# TVHR-PIDer.net
KiCad netlist of a schematic drawn in EAGLE
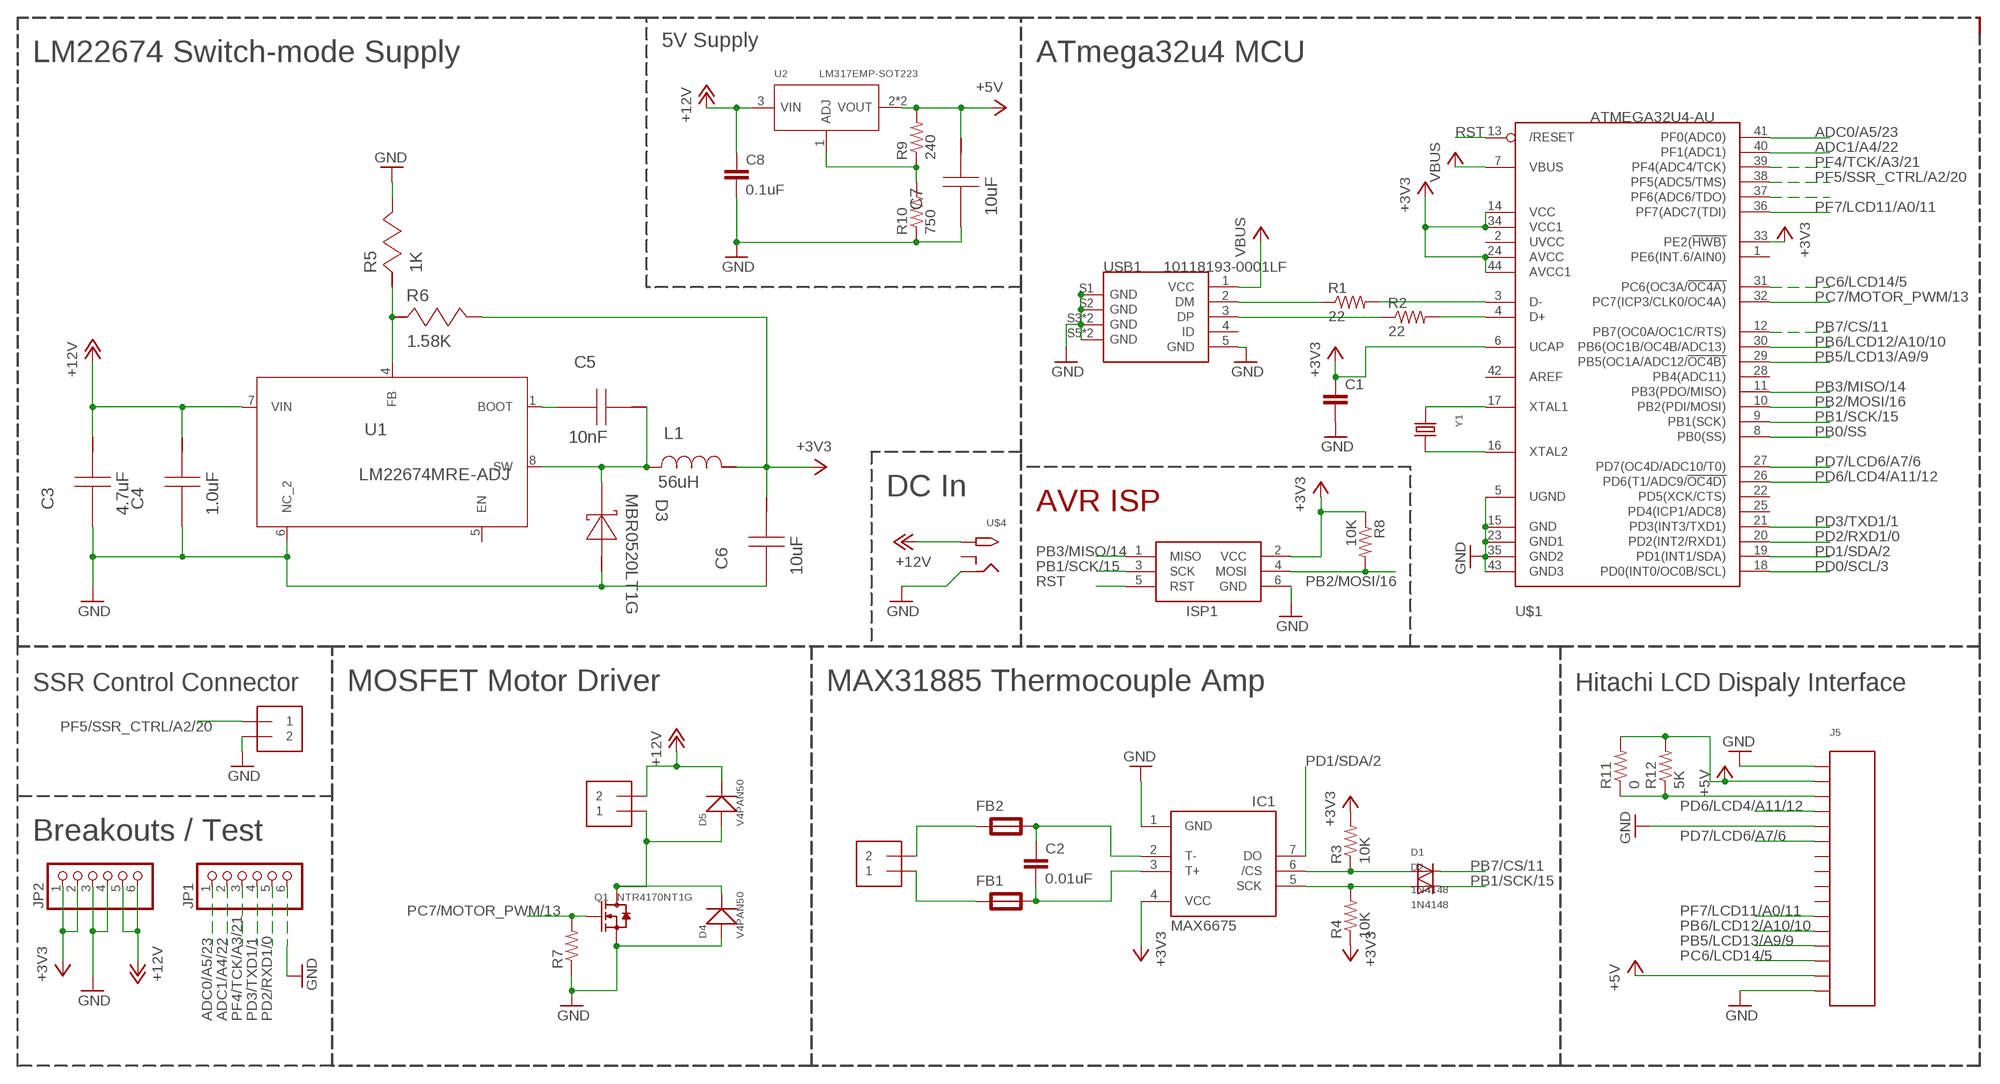
[diagram p0: schematic, sheet 1]

(export (version "E")
  (design (tool "Eeschema 10.0.6"))
  (components
    (comp (ref "C1")
      (value "C-EUC0603")
      (footprint "eagle-import:C0603")
      (libsource (lib "eagle-import") (part "C-EUC0603"))
    )
    (comp (ref "C2")
      (value "0.01uF")
      (footprint "eagle-import:C0603")
      (libsource (lib "eagle-import") (part "C-EUC0603"))
    )
    (comp (ref "C3")
      (value "4.7uF")
      (footprint "eagle-import:0805")
      (fields (field (name "MANUFACTURER_PART_NUMBER") "GRM21BR61E475KA12L"))
      (libsource (lib "eagle-import") (part "GRM21BR61E475KA12L"))
    )
    (comp (ref "C4")
      (value "1.0uF")
      (footprint "eagle-import:0603")
      (fields (field (name "MANUFACTURER_PART_NUMBER") "GRM188R71C105KA12D"))
      (libsource (lib "eagle-import") (part "GRM188R71C105KA12D"))
    )
    (comp (ref "C5")
      (value "10nF")
      (footprint "eagle-import:0805")
      (fields (field (name "MANUFACTURER_PART_NUMBER") "C0805C103K5RACTU"))
      (libsource (lib "eagle-import") (part "C0805C103K5RACTU"))
    )
    (comp (ref "C6")
      (value "10uF")
      (footprint "eagle-import:0805")
      (fields (field (name "MANUFACTURER_PART_NUMBER") "GRM219R60J106KE19D"))
      (libsource (lib "eagle-import") (part "GRM219R60J106KE19D"))
    )
    (comp (ref "C7")
      (value "10uF")
      (footprint "eagle-import:0805")
      (fields (field (name "MANUFACTURER_PART_NUMBER") "GRM219R60J106KE19D"))
      (libsource (lib "eagle-import") (part "GRM219R60J106KE19D"))
    )
    (comp (ref "C8")
      (value "0.1uF")
      (footprint "eagle-import:C0603")
      (libsource (lib "eagle-import") (part "C-EUC0603"))
    )
    (comp (ref "D1")
      (value "1N4148")
      (footprint "eagle-import:SOD-323F")
      (libsource (lib "eagle-import") (part "DIODESOD-323F"))
    )
    (comp (ref "D2")
      (value "1N4148")
      (footprint "eagle-import:SOD-323F")
      (libsource (lib "eagle-import") (part "DIODESOD-323F"))
    )
    (comp (ref "D3")
      (value "MBR0520LT1G")
      (footprint "eagle-import:SOD-123")
      (libsource (lib "eagle-import") (part "MBR0520LT1G"))
    )
    (comp (ref "D4")
      (value "V4PAN50")
      (footprint "eagle-import:SMD-DIODE-DO221BC-2")
      (fields (field (name "MF") "VISHAY"))
      (libsource (lib "eagle-import") (part "SMD-DIODE-50V-4A(DO-221BC)"))
    )
    (comp (ref "D5")
      (value "V4PAN50")
      (footprint "eagle-import:SMD-DIODE-DO221BC-2")
      (fields (field (name "MF") "VISHAY"))
      (libsource (lib "eagle-import") (part "SMD-DIODE-50V-4A(DO-221BC)"))
    )
    (comp (ref "FB1")
      (value "FERRITE-BEAD")
      (footprint "eagle-import:R0805")
      (libsource (lib "eagle-import") (part "FERRITE-BEAD"))
    )
    (comp (ref "FB2")
      (value "FERRITE-BEAD")
      (footprint "eagle-import:R0805")
      (libsource (lib "eagle-import") (part "FERRITE-BEAD"))
    )
    (comp (ref "IC1")
      (value "MAX6675")
      (footprint "eagle-import:SO08")
      (libsource (lib "eagle-import") (part "MAX6675"))
    )
    (comp (ref "ISP1")
      (value "AVRISP-BOX")
      (footprint "eagle-import:AVRISP-BOX")
      (libsource (lib "eagle-import") (part "AVRISP-BOX"))
    )
    (comp (ref "J2")
      (value "1X2-3.5MM")
      (footprint "eagle-import:1X2-3.5MM")
      (libsource (lib "eagle-import") (part "1X2-3.5MM"))
    )
    (comp (ref "J3")
      (value "1X2-3.5MM")
      (footprint "eagle-import:1X2-3.5MM")
      (libsource (lib "eagle-import") (part "1X2-3.5MM"))
    )
    (comp (ref "J4")
      (value "1X2-3.5MM")
      (footprint "eagle-import:1X2-3.5MM")
      (libsource (lib "eagle-import") (part "1X2-3.5MM"))
    )
    (comp (ref "J5")
      (value "16X2-CHAR-LCD-MODULE")
      (footprint "eagle-import:H16-2.54")
      (libsource (lib "eagle-import") (part "16X2-CHAR-LCD-MODULE"))
    )
    (comp (ref "JP1")
      (value "PINHD-1X6")
      (footprint "eagle-import:1X06")
      (libsource (lib "eagle-import") (part "PINHD-1X6"))
    )
    (comp (ref "JP2")
      (value "PINHD-1X6")
      (footprint "eagle-import:1X06")
      (libsource (lib "eagle-import") (part "PINHD-1X6"))
    )
    (comp (ref "L1")
      (value "56uH")
      (footprint "eagle-import:ELL6UH")
      (fields (field (name "MANUFACTURER_PART_NUMBER") "ELL-6UH560M"))
      (libsource (lib "eagle-import") (part "ELL-6UH560M"))
    )
    (comp (ref "Q1")
      (value "NTR4170NT1G")
      (footprint "eagle-import:SOT-23")
      (fields (field (name "MPN") "NTR4170N"))
      (libsource (lib "eagle-import") (part "SMD-MOSFET-N-CHAN-30V-3.1A-NTR4170N(SOT23)"))
    )
    (comp (ref "R1")
      (value "22")
      (footprint "eagle-import:R0603")
      (libsource (lib "eagle-import") (part "R-US_R0603"))
    )
    (comp (ref "R2")
      (value "22")
      (footprint "eagle-import:R0603")
      (libsource (lib "eagle-import") (part "R-US_R0603"))
    )
    (comp (ref "R3")
      (value "10K")
      (footprint "eagle-import:R0603")
      (libsource (lib "eagle-import") (part "R-US_R0603"))
    )
    (comp (ref "R4")
      (value "10K")
      (footprint "eagle-import:R0603")
      (libsource (lib "eagle-import") (part "R-US_R0603"))
    )
    (comp (ref "R5")
      (value "1K")
      (footprint "eagle-import:0805")
      (fields
        (field (name "MANUFACTURER_PART_NUMBER") "ERJ-6ENF1001V")
        (field (name "POWER") "0.125")
        (field (name "TOLERANCE") "1.0")
      )
      (libsource (lib "eagle-import") (part "ERJ-6ENF1001V"))
    )
    (comp (ref "R6")
      (value "1.58K")
      (footprint "eagle-import:0805")
      (fields
        (field (name "MANUFACTURER_PART_NUMBER") "ERJ-6ENF1581V")
        (field (name "POWER") "0.125")
        (field (name "TOLERANCE") "1.0")
      )
      (libsource (lib "eagle-import") (part "ERJ-6ENF1581V"))
    )
    (comp (ref "R7")
      (value "R-US_R0603")
      (footprint "eagle-import:R0603")
      (libsource (lib "eagle-import") (part "R-US_R0603"))
    )
    (comp (ref "R8")
      (value "10K")
      (footprint "eagle-import:R0603")
      (libsource (lib "eagle-import") (part "R-US_R0603"))
    )
    (comp (ref "R9")
      (value "240")
      (footprint "eagle-import:R0603")
      (libsource (lib "eagle-import") (part "R-US_R0603"))
    )
    (comp (ref "R10")
      (value "750")
      (footprint "eagle-import:R0603")
      (libsource (lib "eagle-import") (part "R-US_R0603"))
    )
    (comp (ref "R11")
      (value "0")
      (footprint "eagle-import:R0603")
      (libsource (lib "eagle-import") (part "R-US_R0603"))
    )
    (comp (ref "R12")
      (value "5K")
      (footprint "eagle-import:R0603")
      (libsource (lib "eagle-import") (part "R-US_R0603"))
    )
    (comp (ref "U$1")
      (value "ATMEGA32U4-AU")
      (footprint "eagle-import:TQFP44")
      (libsource (lib "eagle-import") (part "ATMEGA32U4-AU"))
    )
    (comp (ref "U$4")
      (value "2.1MMJACKTHM")
      (footprint "eagle-import:PJ-102A")
      (libsource (lib "eagle-import") (part "2.1MMJACKTHM"))
    )
    (comp (ref "U1")
      (value "LM22674MRE-ADJ")
      (footprint "eagle-import:MRA08B")
      (fields (field (name "MANUFACTURER_PART_NUMBER") "LM22674MRE-ADJ/NOPB"))
      (libsource (lib "eagle-import") (part "LM22674MRE-ADJ/NOPB"))
    )
    (comp (ref "U2")
      (value "LM317EMP-SOT223")
      (footprint "eagle-import:SOT-223")
      (fields (field (name "MPN") "LM317EMP"))
      (libsource (lib "eagle-import") (part "PMIC-LDO-LM317EMP(SOT223)"))
    )
    (comp (ref "USB1")
      (value "10118193-0001LF")
      (footprint "eagle-import:MICRO-USB5+6P-SMD-0.65-B")
      (libsource (lib "eagle-import") (part "MICRO-USB-SMD-B-(10118193-0001LF)"))
    )
    (comp (ref "Y1")
      (value "SMD-XTAL--ABM3B-8.000MHZ-B2-T")
      (footprint "eagle-import:XTAL-SMD-5.0X3.2X1.1MM")
      (fields (field (name "MF") "Abracon") (field (name "MPN") "ABM3B-8.000MHZ-B2-T"))
      (libsource (lib "eagle-import") (part "SMD-XTAL--ABM3B-8.000MHZ-B2-T"))
    )
  )
  (nets
    (net (code "1") (name "+3V3") (class "Default")
      (node (ref "C1") (pin "1") (pinfunction "1_1") (pintype "passive"))
      (node (ref "C6") (pin "1") (pinfunction "1_1") (pintype "passive"))
      (node (ref "IC1") (pin "4") (pinfunction "VCC_4") (pintype "power_in"))
      (node (ref "ISP1") (pin "2") (pinfunction "VCC_2") (pintype "power_in"))
      (node (ref "JP2") (pin "1") (pinfunction "1_1") (pintype "passive"))
      (node (ref "JP2") (pin "2") (pinfunction "2_2") (pintype "passive"))
      (node (ref "L1") (pin "2") (pinfunction "2_2") (pintype "passive"))
      (node (ref "R3") (pin "2") (pinfunction "2_2") (pintype "passive"))
      (node (ref "R4") (pin "1") (pinfunction "1_1") (pintype "passive"))
      (node (ref "R6") (pin "1") (pinfunction "1_1") (pintype "passive"))
      (node (ref "R8") (pin "1") (pinfunction "1_1") (pintype "passive"))
      (node (ref "U$1") (pin "14") (pinfunction "VCC_14") (pintype "bidirectional"))
      (node (ref "U$1") (pin "24") (pinfunction "AVCC_24") (pintype "bidirectional"))
      (node (ref "U$1") (pin "33") (pinfunction "PE2(~{HWB})_33") (pintype "bidirectional"))
      (node (ref "U$1") (pin "34") (pinfunction "VCC1_34") (pintype "bidirectional"))
      (node (ref "U$1") (pin "44") (pinfunction "AVCC1_44") (pintype "bidirectional"))
      (node (ref "U$1") (pin "6") (pinfunction "UCAP_6") (pintype "bidirectional"))
    )
    (net (code "2") (name "+5V") (class "Default")
      (node (ref "C7") (pin "1") (pinfunction "1_1") (pintype "passive"))
      (node (ref "J5") (pin "15") (pinfunction "P$15_15") (pintype "passive"))
      (node (ref "J5") (pin "2") (pinfunction "P$2_2") (pintype "passive"))
      (node (ref "R11") (pin "2") (pinfunction "2_2") (pintype "passive"))
      (node (ref "R12") (pin "2") (pinfunction "2_2") (pintype "passive"))
      (node (ref "R9") (pin "2") (pinfunction "2_2") (pintype "passive"))
      (node (ref "U2") (pin "2") (pinfunction "VOUT_2") (pintype "bidirectional"))
      (node (ref "U2") (pin "TER") (pinfunction "VOUT_TER") (pintype "bidirectional"))
    )
    (net (code "3") (name "+12V") (class "Default")
      (node (ref "C3") (pin "1") (pinfunction "1_1") (pintype "passive"))
      (node (ref "C4") (pin "1") (pinfunction "1_1") (pintype "passive"))
      (node (ref "C8") (pin "1") (pinfunction "1_1") (pintype "passive"))
      (node (ref "D5") (pin "P$2") (pinfunction "-_P$2") (pintype "passive"))
      (node (ref "J4") (pin "2") (pinfunction "2_2") (pintype "passive"))
      (node (ref "JP2") (pin "5") (pinfunction "5_5") (pintype "passive"))
      (node (ref "JP2") (pin "6") (pinfunction "6_6") (pintype "passive"))
      (node (ref "U$4") (pin "TIP") (pinfunction "TIP_TIP") (pintype "bidirectional"))
      (node (ref "U1") (pin "7") (pinfunction "VIN_7") (pintype "passive"))
      (node (ref "U2") (pin "3") (pinfunction "VIN_3") (pintype "bidirectional"))
    )
    (net (code "4") (name "/ADC0{slash}A5{slash}23") (class "Default")
      (node (ref "JP1") (pin "1") (pinfunction "1_1") (pintype "passive"))
      (node (ref "U$1") (pin "41") (pinfunction "PF0(ADC0)_41") (pintype "bidirectional"))
    )
    (net (code "5") (name "/ADC1{slash}A4{slash}22") (class "Default")
      (node (ref "JP1") (pin "2") (pinfunction "2_2") (pintype "passive"))
      (node (ref "U$1") (pin "40") (pinfunction "PF1(ADC1)_40") (pintype "bidirectional"))
    )
    (net (code "6") (name "/PB0{slash}SS") (class "Default")
      (node (ref "U$1") (pin "8") (pinfunction "PB0(SS)_8") (pintype "bidirectional"))
    )
    (net (code "7") (name "/PB1{slash}SCK{slash}15") (class "Default")
      (node (ref "D2") (pin "A") (pinfunction "A_A") (pintype "passive"))
      (node (ref "D2") (pin "C") (pinfunction "C_C") (pintype "passive"))
      (node (ref "IC1") (pin "5") (pinfunction "SCK_5") (pintype "input"))
      (node (ref "ISP1") (pin "3") (pinfunction "SCK_3") (pintype "output"))
      (node (ref "R4") (pin "2") (pinfunction "2_2") (pintype "passive"))
      (node (ref "U$1") (pin "9") (pinfunction "PB1(SCK)_9") (pintype "bidirectional"))
    )
    (net (code "8") (name "/PB2{slash}MOSI{slash}16") (class "Default")
      (node (ref "ISP1") (pin "4") (pinfunction "MOSI_4") (pintype "output"))
      (node (ref "R8") (pin "2") (pinfunction "2_2") (pintype "passive"))
      (node (ref "U$1") (pin "10") (pinfunction "PB2(PDI/MOSI)_10") (pintype "bidirectional"))
    )
    (net (code "9") (name "/PB3{slash}MISO{slash}14") (class "Default")
      (node (ref "ISP1") (pin "1") (pinfunction "MISO_1") (pintype "input"))
      (node (ref "U$1") (pin "11") (pinfunction "PB3(PDO/MISO)_11") (pintype "bidirectional"))
    )
    (net (code "10") (name "/PB5{slash}LCD13{slash}A9{slash}9") (class "Default")
      (node (ref "J5") (pin "13") (pinfunction "P$13_13") (pintype "passive"))
      (node (ref "U$1") (pin "29") (pinfunction "PB5(OC1A/ADC12/~{OC4B})_29") (pintype "bidirectional"))
    )
    (net (code "11") (name "/PB6{slash}LCD12{slash}A10{slash}10") (class "Default")
      (node (ref "J5") (pin "12") (pinfunction "P$12_12") (pintype "passive"))
      (node (ref "U$1") (pin "30") (pinfunction "PB6(OC1B/OC4B/ADC13)_30") (pintype "bidirectional"))
    )
    (net (code "12") (name "/PB7{slash}CS{slash}11") (class "Default")
      (node (ref "D1") (pin "A") (pinfunction "A_A") (pintype "passive"))
      (node (ref "D1") (pin "C") (pinfunction "C_C") (pintype "passive"))
      (node (ref "IC1") (pin "6") (pinfunction "/CS_6") (pintype "input"))
      (node (ref "R3") (pin "1") (pinfunction "1_1") (pintype "passive"))
      (node (ref "U$1") (pin "12") (pinfunction "PB7(OC0A/OC1C/RTS)_12") (pintype "bidirectional"))
    )
    (net (code "13") (name "/PC6{slash}LCD14{slash}5") (class "Default")
      (node (ref "J5") (pin "14") (pinfunction "P$14_14") (pintype "passive"))
      (node (ref "U$1") (pin "31") (pinfunction "PC6(OC3A/~{OC4A})_31") (pintype "bidirectional"))
    )
    (net (code "14") (name "/PC7{slash}MOTOR_PWM{slash}13") (class "Default")
      (node (ref "Q1") (pin "1") (pinfunction "G_1") (pintype "passive"))
      (node (ref "R7") (pin "2") (pinfunction "2_2") (pintype "passive"))
      (node (ref "U$1") (pin "32") (pinfunction "PC7(ICP3/CLK0/OC4A)_32") (pintype "bidirectional"))
    )
    (net (code "15") (name "/PD0{slash}SCL{slash}3") (class "Default")
      (node (ref "U$1") (pin "18") (pinfunction "PD0(INT0/OC0B/SCL)_18") (pintype "bidirectional"))
    )
    (net (code "16") (name "/PD1{slash}SDA{slash}2") (class "Default")
      (node (ref "IC1") (pin "7") (pinfunction "DO_7") (pintype "output"))
      (node (ref "U$1") (pin "19") (pinfunction "PD1(INT1/SDA)_19") (pintype "bidirectional"))
    )
    (net (code "17") (name "/PD2{slash}RXD1{slash}0") (class "Default")
      (node (ref "JP1") (pin "5") (pinfunction "5_5") (pintype "passive"))
      (node (ref "U$1") (pin "20") (pinfunction "PD2(INT2/RXD1)_20") (pintype "bidirectional"))
    )
    (net (code "18") (name "/PD3{slash}TXD1{slash}1") (class "Default")
      (node (ref "JP1") (pin "4") (pinfunction "4_4") (pintype "passive"))
      (node (ref "U$1") (pin "21") (pinfunction "PD3(INT3/TXD1)_21") (pintype "bidirectional"))
    )
    (net (code "19") (name "/PD6{slash}LCD4{slash}A11{slash}12") (class "Default")
      (node (ref "J5") (pin "4") (pinfunction "P$4_4") (pintype "passive"))
      (node (ref "U$1") (pin "26") (pinfunction "PD6(T1/ADC9/~{OC4D})_26") (pintype "bidirectional"))
    )
    (net (code "20") (name "/PD7{slash}LCD6{slash}A7{slash}6") (class "Default")
      (node (ref "J5") (pin "6") (pinfunction "P$6_6") (pintype "passive"))
      (node (ref "U$1") (pin "27") (pinfunction "PD7(OC4D/ADC10/T0)_27") (pintype "bidirectional"))
    )
    (net (code "21") (name "/PF4{slash}TCK{slash}A3{slash}21") (class "Default")
      (node (ref "JP1") (pin "3") (pinfunction "3_3") (pintype "passive"))
      (node (ref "U$1") (pin "39") (pinfunction "PF4(ADC4/TCK)_39") (pintype "bidirectional"))
    )
    (net (code "22") (name "/PF5{slash}SSR_CTRL{slash}A2{slash}20") (class "Default")
      (node (ref "J3") (pin "1") (pinfunction "1_1") (pintype "passive"))
      (node (ref "U$1") (pin "38") (pinfunction "PF5(ADC5/TMS)_38") (pintype "bidirectional"))
    )
    (net (code "23") (name "/PF7{slash}LCD11{slash}A0{slash}11") (class "Default")
      (node (ref "J5") (pin "11") (pinfunction "P$11_11") (pintype "passive"))
      (node (ref "U$1") (pin "36") (pinfunction "PF7(ADC7(TDI)_36") (pintype "bidirectional"))
    )
    (net (code "24") (name "/RST") (class "Default")
      (node (ref "ISP1") (pin "5") (pinfunction "RST_5") (pintype "output"))
      (node (ref "U$1") (pin "13") (pinfunction "/RESET_13") (pintype "bidirectional"))
    )
    (net (code "25") (name "GND") (class "Default")
      (node (ref "C1") (pin "2") (pinfunction "2_2") (pintype "passive"))
      (node (ref "C3") (pin "2") (pinfunction "2_2") (pintype "passive"))
      (node (ref "C4") (pin "2") (pinfunction "2_2") (pintype "passive"))
      (node (ref "C6") (pin "2") (pinfunction "2_2") (pintype "passive"))
      (node (ref "C7") (pin "2") (pinfunction "2_2") (pintype "passive"))
      (node (ref "C8") (pin "2") (pinfunction "2_2") (pintype "passive"))
      (node (ref "D3") (pin "2") (pinfunction "A_2") (pintype "passive"))
      (node (ref "D4") (pin "P$1") (pinfunction "+_P$1") (pintype "passive"))
      (node (ref "IC1") (pin "1") (pinfunction "GND_1") (pintype "power_in"))
      (node (ref "ISP1") (pin "6") (pinfunction "GND_6") (pintype "power_in"))
      (node (ref "J3") (pin "2") (pinfunction "2_2") (pintype "passive"))
      (node (ref "J5") (pin "1") (pinfunction "P$1_1") (pintype "passive"))
      (node (ref "J5") (pin "16") (pinfunction "P$16_16") (pintype "passive"))
      (node (ref "J5") (pin "5") (pinfunction "P$5_5") (pintype "passive"))
      (node (ref "JP1") (pin "6") (pinfunction "6_6") (pintype "passive"))
      (node (ref "JP2") (pin "3") (pinfunction "3_3") (pintype "passive"))
      (node (ref "JP2") (pin "4") (pinfunction "4_4") (pintype "passive"))
      (node (ref "Q1") (pin "2") (pinfunction "S_2") (pintype "passive"))
      (node (ref "R10") (pin "1") (pinfunction "1_1") (pintype "passive"))
      (node (ref "R5") (pin "1") (pinfunction "1_1") (pintype "passive"))
      (node (ref "R7") (pin "1") (pinfunction "1_1") (pintype "passive"))
      (node (ref "U$1") (pin "15") (pinfunction "GND_15") (pintype "bidirectional"))
      (node (ref "U$1") (pin "23") (pinfunction "GND1_23") (pintype "bidirectional"))
      (node (ref "U$1") (pin "35") (pinfunction "GND2_35") (pintype "bidirectional"))
      (node (ref "U$1") (pin "43") (pinfunction "GND3_43") (pintype "bidirectional"))
      (node (ref "U$1") (pin "5") (pinfunction "UGND_5") (pintype "bidirectional"))
      (node (ref "U$4") (pin "RING") (pinfunction "RING_RING") (pintype "bidirectional"))
      (node (ref "U1") (pin "6") (pinfunction "NC_2_6") (pintype "passive"))
      (node (ref "USB1") (pin "5") (pinfunction "GND_5") (pintype "bidirectional"))
      (node (ref "USB1") (pin "S1") (pinfunction "GND_S1") (pintype "bidirectional"))
      (node (ref "USB1") (pin "S2") (pinfunction "GND_S2") (pintype "bidirectional"))
      (node (ref "USB1") (pin "S3") (pinfunction "GND_S3") (pintype "bidirectional"))
      (node (ref "USB1") (pin "S4") (pinfunction "GND_S4") (pintype "bidirectional"))
      (node (ref "USB1") (pin "S5") (pinfunction "GND_S5") (pintype "bidirectional"))
      (node (ref "USB1") (pin "S6") (pinfunction "GND_S6") (pintype "bidirectional"))
    )
    (net (code "26") (name "Net-(D3-K)") (class "Default")
      (node (ref "C5") (pin "1") (pinfunction "1_1") (pintype "passive"))
      (node (ref "D3") (pin "1") (pinfunction "K_1") (pintype "passive"))
      (node (ref "L1") (pin "1") (pinfunction "1_1") (pintype "passive"))
      (node (ref "U1") (pin "8") (pinfunction "SW_8") (pintype "passive"))
    )
    (net (code "27") (name "Net-(D4--)") (class "Default")
      (node (ref "D4") (pin "P$2") (pinfunction "-_P$2") (pintype "passive"))
      (node (ref "D5") (pin "P$1") (pinfunction "+_P$1") (pintype "passive"))
      (node (ref "J4") (pin "1") (pinfunction "1_1") (pintype "passive"))
      (node (ref "Q1") (pin "3") (pinfunction "D_3") (pintype "passive"))
    )
    (net (code "28") (name "Net-(FB1-Pad1)") (class "Default")
      (node (ref "FB1") (pin "1") (pinfunction "1_1") (pintype "passive"))
      (node (ref "J2") (pin "1") (pinfunction "1_1") (pintype "passive"))
    )
    (net (code "29") (name "Net-(FB2-Pad1)") (class "Default")
      (node (ref "FB2") (pin "1") (pinfunction "1_1") (pintype "passive"))
      (node (ref "J2") (pin "2") (pinfunction "2_2") (pintype "passive"))
    )
    (net (code "30") (name "Net-(IC1-T+)") (class "Default")
      (node (ref "C2") (pin "2") (pinfunction "2_2") (pintype "passive"))
      (node (ref "FB1") (pin "2") (pinfunction "2_2") (pintype "passive"))
      (node (ref "IC1") (pin "3") (pinfunction "T+_3") (pintype "input"))
    )
    (net (code "31") (name "Net-(IC1-T-)") (class "Default")
      (node (ref "C2") (pin "1") (pinfunction "1_1") (pintype "passive"))
      (node (ref "FB2") (pin "2") (pinfunction "2_2") (pintype "passive"))
      (node (ref "IC1") (pin "2") (pinfunction "T-_2") (pintype "input"))
    )
    (net (code "32") (name "Net-(J5-P$3)") (class "Default")
      (node (ref "J5") (pin "3") (pinfunction "P$3_3") (pintype "passive"))
      (node (ref "R11") (pin "1") (pinfunction "1_1") (pintype "passive"))
      (node (ref "R12") (pin "1") (pinfunction "1_1") (pintype "passive"))
    )
    (net (code "33") (name "Net-(U$1-D+)") (class "Default")
      (node (ref "R2") (pin "2") (pinfunction "2_2") (pintype "passive"))
      (node (ref "U$1") (pin "4") (pinfunction "D+_4") (pintype "bidirectional"))
    )
    (net (code "34") (name "Net-(U$1-D-)") (class "Default")
      (node (ref "R1") (pin "2") (pinfunction "2_2") (pintype "passive"))
      (node (ref "U$1") (pin "3") (pinfunction "D-_3") (pintype "bidirectional"))
    )
    (net (code "35") (name "Net-(U$1-XTAL1)") (class "Default")
      (node (ref "U$1") (pin "17") (pinfunction "XTAL1_17") (pintype "bidirectional"))
      (node (ref "Y1") (pin "P$1") (pinfunction "1_P$1") (pintype "passive"))
    )
    (net (code "36") (name "Net-(U$1-XTAL2)") (class "Default")
      (node (ref "U$1") (pin "16") (pinfunction "XTAL2_16") (pintype "bidirectional"))
      (node (ref "Y1") (pin "P$2") (pinfunction "2_P$2") (pintype "passive"))
    )
    (net (code "37") (name "Net-(U1-BOOT)") (class "Default")
      (node (ref "C5") (pin "2") (pinfunction "2_2") (pintype "passive"))
      (node (ref "U1") (pin "1") (pinfunction "BOOT_1") (pintype "passive"))
    )
    (net (code "38") (name "Net-(U1-FB)") (class "Default")
      (node (ref "R5") (pin "2") (pinfunction "2_2") (pintype "passive"))
      (node (ref "R6") (pin "2") (pinfunction "2_2") (pintype "passive"))
      (node (ref "U1") (pin "4") (pinfunction "FB_4") (pintype "passive"))
    )
    (net (code "39") (name "Net-(U2-ADJ)") (class "Default")
      (node (ref "R10") (pin "2") (pinfunction "2_2") (pintype "passive"))
      (node (ref "R9") (pin "1") (pinfunction "1_1") (pintype "passive"))
      (node (ref "U2") (pin "1") (pinfunction "ADJ_1") (pintype "bidirectional"))
    )
    (net (code "40") (name "Net-(USB1-DM)") (class "Default")
      (node (ref "R1") (pin "1") (pinfunction "1_1") (pintype "passive"))
      (node (ref "USB1") (pin "2") (pinfunction "DM_2") (pintype "bidirectional"))
    )
    (net (code "41") (name "Net-(USB1-DP)") (class "Default")
      (node (ref "R2") (pin "1") (pinfunction "1_1") (pintype "passive"))
      (node (ref "USB1") (pin "3") (pinfunction "DP_3") (pintype "bidirectional"))
    )
    (net (code "42") (name "VBUS") (class "Default")
      (node (ref "U$1") (pin "7") (pinfunction "VBUS_7") (pintype "bidirectional"))
      (node (ref "USB1") (pin "1") (pinfunction "VCC_1") (pintype "bidirectional"))
    )
    (net (code "43") (name "unconnected-(J5-P$7-Pad7)") (class "Default")
      (node (ref "J5") (pin "7") (pinfunction "P$7_7") (pintype "passive"))
    )
    (net (code "44") (name "unconnected-(J5-P$8-Pad8)") (class "Default")
      (node (ref "J5") (pin "8") (pinfunction "P$8_8") (pintype "passive"))
    )
    (net (code "45") (name "unconnected-(J5-P$9-Pad9)") (class "Default")
      (node (ref "J5") (pin "9") (pinfunction "P$9_9") (pintype "passive"))
    )
    (net (code "46") (name "unconnected-(J5-P$10-Pad10)") (class "Default")
      (node (ref "J5") (pin "10") (pinfunction "P$10_10") (pintype "passive"))
    )
    (net (code "47") (name "unconnected-(U$1-AREF-Pad42)") (class "Default")
      (node (ref "U$1") (pin "42") (pinfunction "AREF_42") (pintype "bidirectional"))
    )
    (net (code "48") (name "unconnected-(U$1-PB4(ADC11)-Pad28)") (class "Default")
      (node (ref "U$1") (pin "28") (pinfunction "PB4(ADC11)_28") (pintype "bidirectional"))
    )
    (net (code "49") (name "unconnected-(U$1-PD4(ICP1{slash}ADC8)-Pad25)") (class "Default")
      (node (ref "U$1") (pin "25") (pinfunction "PD4(ICP1/ADC8)_25") (pintype "bidirectional"))
    )
    (net (code "50") (name "unconnected-(U$1-PD5(XCK{slash}CTS)-Pad22)") (class "Default")
      (node (ref "U$1") (pin "22") (pinfunction "PD5(XCK/CTS)_22") (pintype "bidirectional"))
    )
    (net (code "51") (name "unconnected-(U$1-PE6(INT.6{slash}AIN0)-Pad1)") (class "Default")
      (node (ref "U$1") (pin "1") (pinfunction "PE6(INT.6/AIN0)_1") (pintype "bidirectional"))
    )
    (net (code "52") (name "unconnected-(U$1-PF6(ADC6{slash}TDO)-Pad37)") (class "Default")
      (node (ref "U$1") (pin "37") (pinfunction "PF6(ADC6/TDO)_37") (pintype "bidirectional"))
    )
    (net (code "53") (name "unconnected-(U$1-UVCC-Pad2)") (class "Default")
      (node (ref "U$1") (pin "2") (pinfunction "UVCC_2") (pintype "bidirectional"))
    )
    (net (code "54") (name "unconnected-(U$4-PadRING_SW)") (class "Default")
      (node (ref "U$4") (pin "RING_SW") (pinfunction "RING_SW_RING_SW") (pintype "bidirectional"))
    )
    (net (code "55") (name "unconnected-(U1-EN-Pad5)") (class "Default")
      (node (ref "U1") (pin "5") (pinfunction "EN_5") (pintype "passive"))
    )
    (net (code "56") (name "unconnected-(USB1-ID-Pad4)") (class "Default")
      (node (ref "USB1") (pin "4") (pinfunction "ID_4") (pintype "bidirectional"))
    )
  )
)
